# test_3.net
KiCad netlist of a schematic drawn in EAGLE
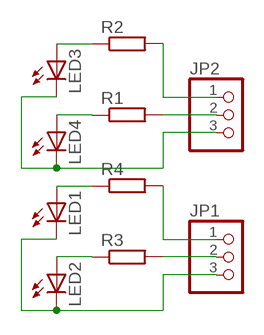
[diagram p0: schematic, sheet 1]

(export (version "E")
  (design (tool "Eeschema 10.0.6"))
  (components
    (comp (ref "JP1")
      (value "PINHD-1X3")
      (footprint "eagle-import:1X03")
      (libsource (lib "eagle-import") (part "PINHD-1X3"))
    )
    (comp (ref "JP2")
      (value "PINHD-1X3")
      (footprint "eagle-import:1X03")
      (libsource (lib "eagle-import") (part "PINHD-1X3"))
    )
    (comp (ref "LED1")
      (value "LED3MM")
      (footprint "eagle-import:LED3MM")
      (libsource (lib "eagle-import") (part "LED3MM"))
    )
    (comp (ref "LED2")
      (value "LED3MM")
      (footprint "eagle-import:LED3MM")
      (libsource (lib "eagle-import") (part "LED3MM"))
    )
    (comp (ref "LED3")
      (value "LED3MM")
      (footprint "eagle-import:LED3MM")
      (libsource (lib "eagle-import") (part "LED3MM"))
    )
    (comp (ref "LED4")
      (value "LED3MM")
      (footprint "eagle-import:LED3MM")
      (libsource (lib "eagle-import") (part "LED3MM"))
    )
    (comp (ref "R1")
      (value "R-EU_0204/7")
      (footprint "eagle-import:0204_7")
      (libsource (lib "eagle-import") (part "R-EU_0204/7"))
    )
    (comp (ref "R2")
      (value "R-EU_0204/7")
      (footprint "eagle-import:0204_7")
      (libsource (lib "eagle-import") (part "R-EU_0204/7"))
    )
    (comp (ref "R3")
      (value "R-EU_0204/7")
      (footprint "eagle-import:0204_7")
      (libsource (lib "eagle-import") (part "R-EU_0204/7"))
    )
    (comp (ref "R4")
      (value "R-EU_0204/7")
      (footprint "eagle-import:0204_7")
      (libsource (lib "eagle-import") (part "R-EU_0204/7"))
    )
  )
  (nets
    (net (code "1") (name "Net-(JP1-Pad1)") (class "Default")
      (node (ref "JP1") (pin "1") (pinfunction "1_1") (pintype "passive"))
      (node (ref "R4") (pin "2") (pinfunction "2_2") (pintype "passive"))
    )
    (net (code "2") (name "Net-(JP1-Pad2)") (class "Default")
      (node (ref "JP1") (pin "2") (pinfunction "2_2") (pintype "passive"))
      (node (ref "R3") (pin "2") (pinfunction "2_2") (pintype "passive"))
    )
    (net (code "3") (name "Net-(JP2-Pad1)") (class "Default")
      (node (ref "JP2") (pin "1") (pinfunction "1_1") (pintype "passive"))
      (node (ref "R2") (pin "2") (pinfunction "2_2") (pintype "passive"))
    )
    (net (code "4") (name "Net-(JP2-Pad2)") (class "Default")
      (node (ref "JP2") (pin "2") (pinfunction "2_2") (pintype "passive"))
      (node (ref "R1") (pin "2") (pinfunction "2_2") (pintype "passive"))
    )
    (net (code "5") (name "Net-(LED1-C)") (class "Default")
      (node (ref "JP1") (pin "3") (pinfunction "3_3") (pintype "passive"))
      (node (ref "LED1") (pin "K") (pinfunction "C_K") (pintype "passive"))
      (node (ref "LED2") (pin "K") (pinfunction "C_K") (pintype "passive"))
    )
    (net (code "6") (name "Net-(LED1-PadA)") (class "Default")
      (node (ref "LED1") (pin "A") (pinfunction "A_A") (pintype "passive"))
      (node (ref "R4") (pin "1") (pinfunction "1_1") (pintype "passive"))
    )
    (net (code "7") (name "Net-(LED2-PadA)") (class "Default")
      (node (ref "LED2") (pin "A") (pinfunction "A_A") (pintype "passive"))
      (node (ref "R3") (pin "1") (pinfunction "1_1") (pintype "passive"))
    )
    (net (code "8") (name "Net-(LED3-C)") (class "Default")
      (node (ref "JP2") (pin "3") (pinfunction "3_3") (pintype "passive"))
      (node (ref "LED3") (pin "K") (pinfunction "C_K") (pintype "passive"))
      (node (ref "LED4") (pin "K") (pinfunction "C_K") (pintype "passive"))
    )
    (net (code "9") (name "Net-(LED3-PadA)") (class "Default")
      (node (ref "LED3") (pin "A") (pinfunction "A_A") (pintype "passive"))
      (node (ref "R2") (pin "1") (pinfunction "1_1") (pintype "passive"))
    )
    (net (code "10") (name "Net-(LED4-PadA)") (class "Default")
      (node (ref "LED4") (pin "A") (pinfunction "A_A") (pintype "passive"))
      (node (ref "R1") (pin "1") (pinfunction "1_1") (pintype "passive"))
    )
  )
)
